# overview_mcu_dev.net
KiCad netlist of a schematic drawn in EAGLE
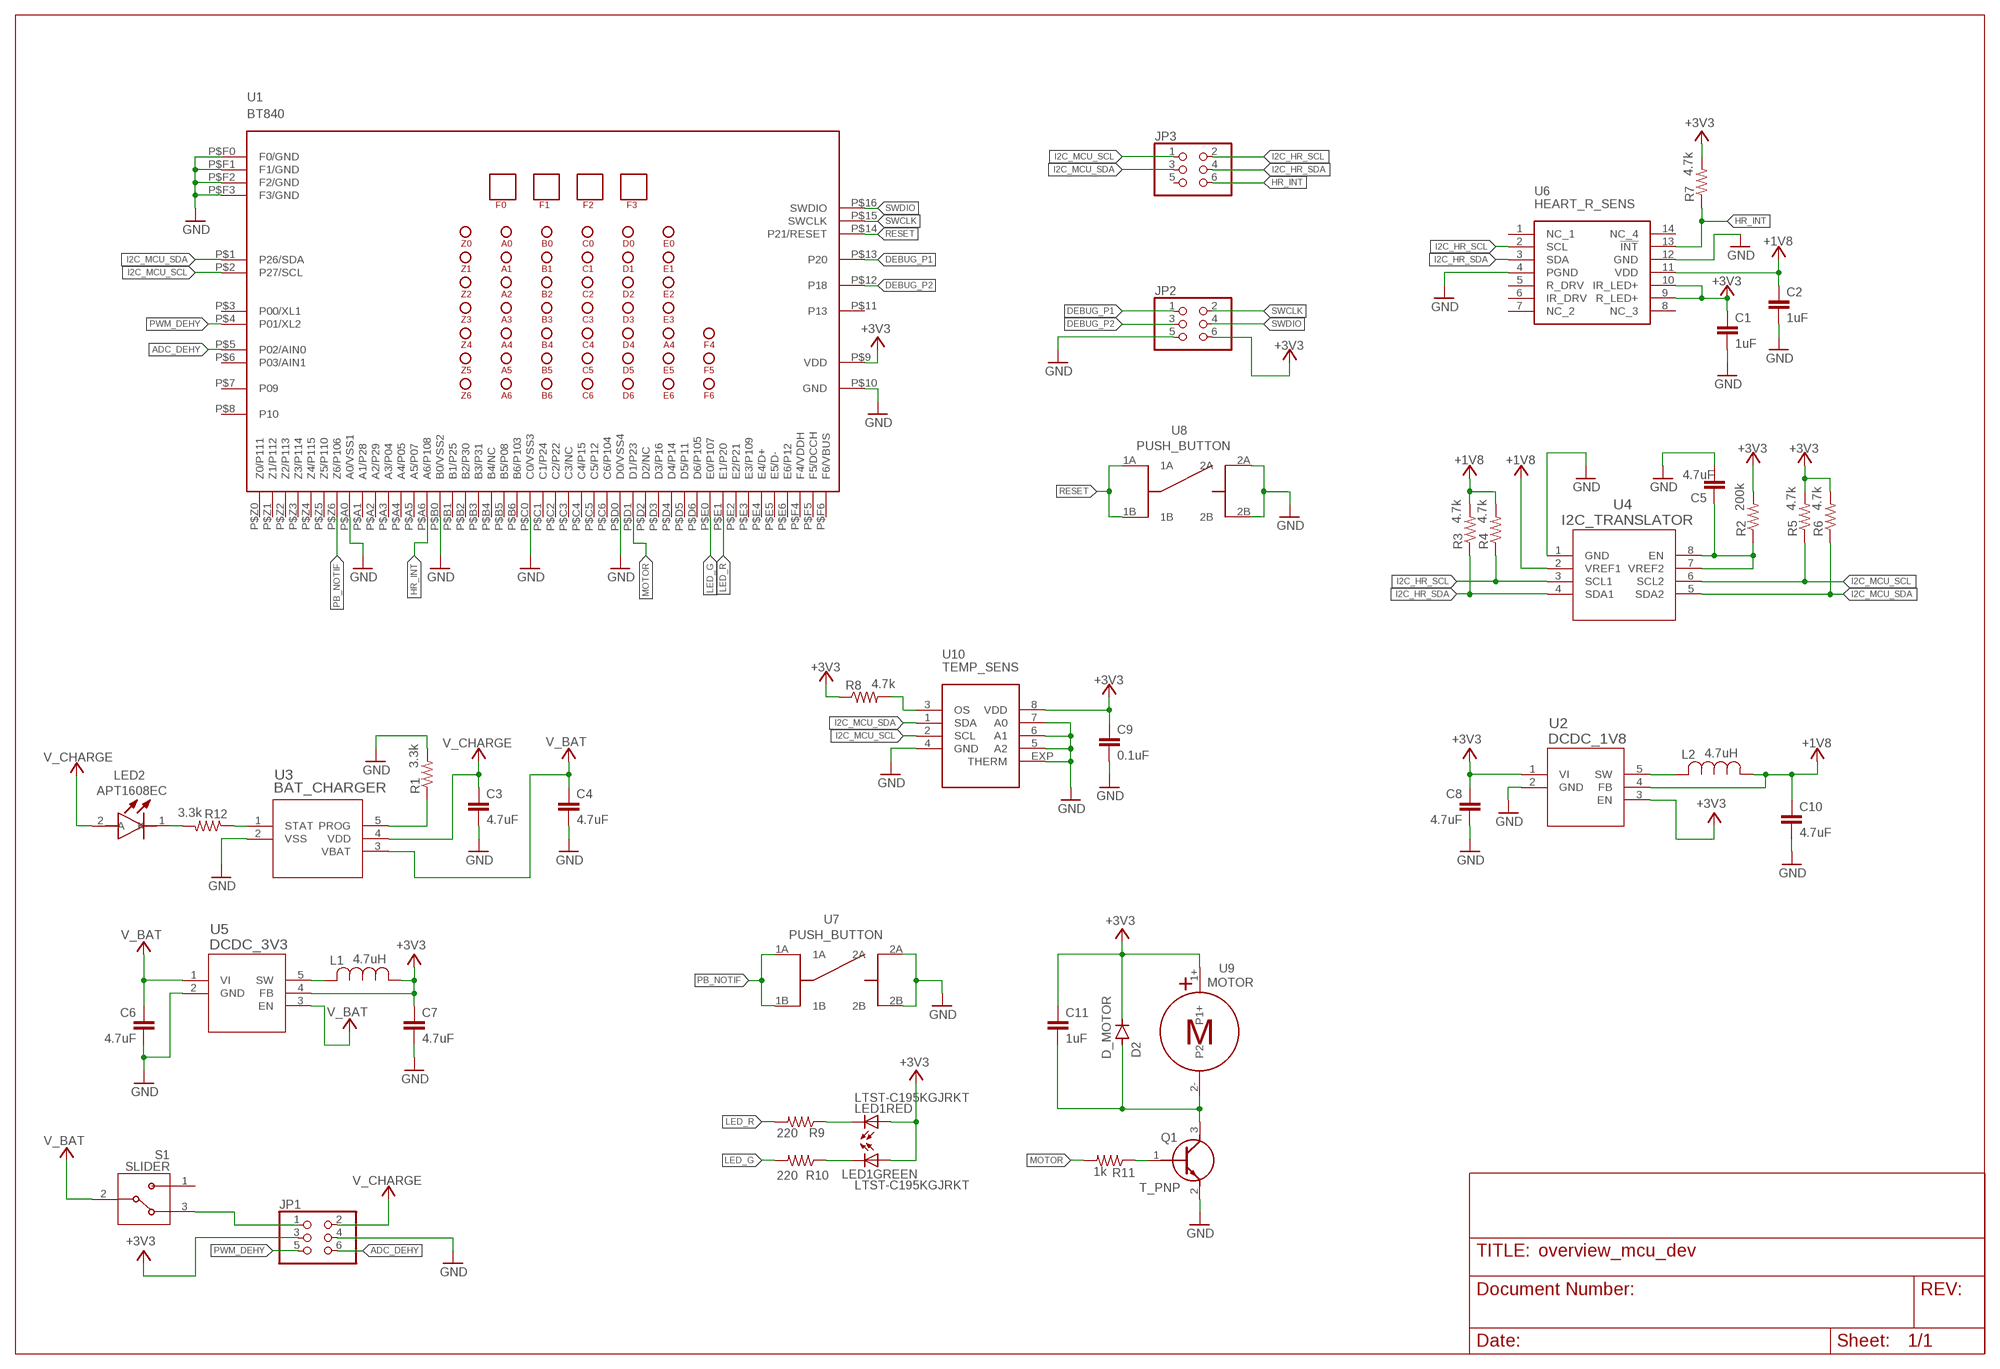
[diagram p0: schematic, sheet 1]

(export (version "E")
  (design (tool "Eeschema 10.0.6"))
  (components
    (comp (ref "C1")
      (value "1uF")
      (footprint "eagle-import:C0402K")
      (libsource (lib "eagle-import") (part "C-EUC0402K"))
    )
    (comp (ref "C2")
      (value "1uF")
      (footprint "eagle-import:C0402K")
      (libsource (lib "eagle-import") (part "C-EUC0402K"))
    )
    (comp (ref "C3")
      (value "4.7uF")
      (footprint "eagle-import:C0402K")
      (libsource (lib "eagle-import") (part "C-EUC0402K"))
    )
    (comp (ref "C4")
      (value "4.7uF")
      (footprint "eagle-import:C0402K")
      (libsource (lib "eagle-import") (part "C-EUC0402K"))
    )
    (comp (ref "C5")
      (value "4.7uF")
      (footprint "eagle-import:C0402K")
      (libsource (lib "eagle-import") (part "C-EUC0402K"))
    )
    (comp (ref "C6")
      (value "4.7uF")
      (footprint "eagle-import:C0402K")
      (libsource (lib "eagle-import") (part "C-EUC0402K"))
    )
    (comp (ref "C7")
      (value "4.7uF")
      (footprint "eagle-import:C0402K")
      (libsource (lib "eagle-import") (part "C-EUC0402K"))
    )
    (comp (ref "C8")
      (value "4.7uF")
      (footprint "eagle-import:C0402K")
      (libsource (lib "eagle-import") (part "C-EUC0402K"))
    )
    (comp (ref "C9")
      (value "0.1uF")
      (footprint "eagle-import:C0402K")
      (libsource (lib "eagle-import") (part "C-EUC0402K"))
    )
    (comp (ref "C10")
      (value "4.7uF")
      (footprint "eagle-import:C0402K")
      (libsource (lib "eagle-import") (part "C-EUC0402K"))
    )
    (comp (ref "C11")
      (value "1uF")
      (footprint "eagle-import:C0402K")
      (libsource (lib "eagle-import") (part "C-EUC0402K"))
    )
    (comp (ref "D2")
      (value "D_MOTOR")
      (footprint "eagle-import:SOD-123_MINI-SMA")
      (libsource (lib "eagle-import") (part "CGRM400-G1"))
    )
    (comp (ref "JP1")
      (value "PINHD-2X3")
      (footprint "eagle-import:2X03")
      (libsource (lib "eagle-import") (part "PINHD-2X3"))
    )
    (comp (ref "JP2")
      (value "PINHD-2X3")
      (footprint "eagle-import:2X03")
      (libsource (lib "eagle-import") (part "PINHD-2X3"))
    )
    (comp (ref "JP3")
      (value "PINHD-2X3")
      (footprint "eagle-import:2X03")
      (libsource (lib "eagle-import") (part "PINHD-2X3"))
    )
    (comp (ref "L1")
      (value "4.7uH")
      (footprint "eagle-import:IND_1608")
      (fields (field (name "MANUFACTURER_PART_NUMBER") "GLFR1608T4R7MLR"))
      (libsource (lib "eagle-import") (part "L_0604"))
    )
    (comp (ref "L2")
      (value "4.7uH")
      (footprint "eagle-import:IND_1608")
      (fields (field (name "MANUFACTURER_PART_NUMBER") "GLFR1608T4R7MLR"))
      (libsource (lib "eagle-import") (part "L_0604"))
    )
    (comp (ref "LED1")
      (value "LTST-C195KGJRKT")
      (footprint "eagle-import:LED-SMT")
      (fields
        (field (name "MANUFACTURER") "Lite-On Inc.")
        (field (name "MANUFACTURER_PART_NUM") "LTST-C195KGJRKT ")
      )
      (libsource (lib "eagle-import") (part "LTST-C195KGJRKT"))
    )
    (comp (ref "LED2")
      (value "APT1608EC")
      (footprint "eagle-import:LEDC1608X85N")
      (fields (field (name "MANUFACTURER") "Kingbright"))
      (libsource (lib "eagle-import") (part "APT1608EC"))
    )
    (comp (ref "Q1")
      (value "T_PNP")
      (footprint "eagle-import:SOT95P240X93-3N")
      (fields
        (field (name "MANUFACTURER") "Micro Commercial Co")
        (field (name "MANUFACTURER_PART_NUM") "MMBT3904-TP ")
      )
      (libsource (lib "eagle-import") (part "T_PNP"))
    )
    (comp (ref "R1")
      (value "3.3k")
      (footprint "eagle-import:R0402")
      (libsource (lib "eagle-import") (part "R-US_R0402"))
    )
    (comp (ref "R2")
      (value "200k")
      (footprint "eagle-import:R0402")
      (libsource (lib "eagle-import") (part "R-US_R0402"))
    )
    (comp (ref "R3")
      (value "4.7k")
      (footprint "eagle-import:R0402")
      (libsource (lib "eagle-import") (part "R-US_R0402"))
    )
    (comp (ref "R4")
      (value "4.7k")
      (footprint "eagle-import:R0402")
      (libsource (lib "eagle-import") (part "R-US_R0402"))
    )
    (comp (ref "R5")
      (value "4.7k")
      (footprint "eagle-import:R0402")
      (libsource (lib "eagle-import") (part "R-US_R0402"))
    )
    (comp (ref "R6")
      (value "4.7k")
      (footprint "eagle-import:R0402")
      (libsource (lib "eagle-import") (part "R-US_R0402"))
    )
    (comp (ref "R7")
      (value "4.7k")
      (footprint "eagle-import:R0402")
      (libsource (lib "eagle-import") (part "R-US_R0402"))
    )
    (comp (ref "R8")
      (value "4.7k")
      (footprint "eagle-import:R0402")
      (libsource (lib "eagle-import") (part "R-US_R0402"))
    )
    (comp (ref "R9")
      (value "220")
      (footprint "eagle-import:R0402")
      (libsource (lib "eagle-import") (part "R-US_R0402"))
    )
    (comp (ref "R10")
      (value "220")
      (footprint "eagle-import:R0402")
      (libsource (lib "eagle-import") (part "R-US_R0402"))
    )
    (comp (ref "R11")
      (value "1k")
      (footprint "eagle-import:R0402")
      (libsource (lib "eagle-import") (part "R-US_R0402"))
    )
    (comp (ref "R12")
      (value "3.3k")
      (footprint "eagle-import:R0402")
      (libsource (lib "eagle-import") (part "R-US_R0402"))
    )
    (comp (ref "S1")
      (value "SLIDER")
      (footprint "eagle-import:SW_CJS-1200TA")
      (fields
        (field (name "MANUFACTURER") "Nidec Copal Electronics")
        (field (name "MANUFACTURER_PART") "CJS-1200TA ")
      )
      (libsource (lib "eagle-import") (part "SLIDER"))
    )
    (comp (ref "U1")
      (value "BT840")
      (footprint "eagle-import:BT840")
      (fields (field (name "MANUFACTURER") "Fanstel"))
      (libsource (lib "eagle-import") (part "BT840"))
    )
    (comp (ref "U2")
      (value "DCDC_1V8")
      (footprint "eagle-import:DBV5")
      (fields
        (field (name "MANUFACTURER") "Texas Instruments")
        (field (name "MANUFACTURER_PART_NUM") "TPS62202DBVR")
      )
      (libsource (lib "eagle-import") (part "DCDC_1V8"))
    )
    (comp (ref "U3")
      (value "BAT_CHARGER")
      (footprint "eagle-import:SOT-23-5_MC")
      (fields
        (field (name "MANUFACTURER") "Microchip")
        (field (name "MANUFACTURER_PART_NUM") "MCP73831T2ACIOT")
      )
      (libsource (lib "eagle-import") (part "BAT_CHARGER"))
    )
    (comp (ref "U4")
      (value "I2C_TRANSLATOR")
      (footprint "eagle-import:DQE8")
      (fields
        (field (name "MANUFACTURER") "Texas Instruments")
        (field (name "MANUFACTURER_PART_NUM") "PCA9306DQER")
      )
      (libsource (lib "eagle-import") (part "I2C_TRANSLATOR"))
    )
    (comp (ref "U5")
      (value "DCDC_3V3")
      (footprint "eagle-import:DBV5")
      (fields
        (field (name "MANUFACTURER") "Texas Instruments")
        (field (name "MANUFACTURER_PART_NUM") "TPS62203DBVR")
      )
      (libsource (lib "eagle-import") (part "DCDC_3V3"))
    )
    (comp (ref "U6")
      (value "HEART_R_SENS")
      (footprint "eagle-import:MAX30102")
      (fields
        (field (name "MANUFACTURER") "Maxim Integrated")
        (field (name "MANUFACTURER_PART_NUM") "MAX30102EFD+")
      )
      (libsource (lib "eagle-import") (part "HEART_R_SENS"))
    )
    (comp (ref "U7")
      (value "PUSH_BUTTON")
      (footprint "eagle-import:PUSH_BUTTON")
      (fields
        (field (name "MANUFACTURER") " Panasonic Electronic Components")
        (field (name "MANUFACTURER_PART_NUM") "EVQ-P7A01P ")
      )
      (libsource (lib "eagle-import") (part "PUSH_BUTTON"))
    )
    (comp (ref "U8")
      (value "PUSH_BUTTON")
      (footprint "eagle-import:PUSH_BUTTON")
      (fields
        (field (name "MANUFACTURER") " Panasonic Electronic Components")
        (field (name "MANUFACTURER_PART_NUM") "EVQ-P7A01P ")
      )
      (libsource (lib "eagle-import") (part "PUSH_BUTTON"))
    )
    (comp (ref "U9")
      (value "MOTOR")
      (footprint "eagle-import:MOTOR")
      (fields
        (field (name "MANUFACTURER") "Jinlong Machinery & Electronics, Inc.")
        (field (name "MANUFACTURER_PART_NUM") "Z4FC1B1301781")
      )
      (libsource (lib "eagle-import") (part "MOTOR"))
    )
    (comp (ref "U10")
      (value "TEMP_SENS")
      (footprint "eagle-import:MAX30205")
      (fields
        (field (name "MANUFACTURER") "Maxim Integrated")
        (field (name "MANUFACTURER_PART_NUM") "MAX30205MTA+")
      )
      (libsource (lib "eagle-import") (part "TEMP_SENS"))
    )
  )
  (nets
    (net (code "1") (name "+1V8") (class "Default")
      (node (ref "C10") (pin "1") (pinfunction "1_1") (pintype "passive"))
      (node (ref "C2") (pin "1") (pinfunction "1_1") (pintype "passive"))
      (node (ref "L2") (pin "1") (pinfunction "1_1") (pintype "passive"))
      (node (ref "R3") (pin "2") (pinfunction "2_2") (pintype "passive"))
      (node (ref "R4") (pin "2") (pinfunction "2_2") (pintype "passive"))
      (node (ref "U2") (pin "4") (pinfunction "FB_4") (pintype "input"))
      (node (ref "U4") (pin "2") (pinfunction "VREF1_2") (pintype "passive"))
      (node (ref "U6") (pin "11") (pinfunction "VDD_11") (pintype "bidirectional"))
    )
    (net (code "2") (name "+3V3") (class "Default")
      (node (ref "C1") (pin "1") (pinfunction "1_1") (pintype "passive"))
      (node (ref "C11") (pin "1") (pinfunction "1_1") (pintype "passive"))
      (node (ref "C7") (pin "1") (pinfunction "1_1") (pintype "passive"))
      (node (ref "C8") (pin "1") (pinfunction "1_1") (pintype "passive"))
      (node (ref "C9") (pin "1") (pinfunction "1_1") (pintype "passive"))
      (node (ref "D2") (pin "C") (pinfunction "C_C") (pintype "passive"))
      (node (ref "JP1") (pin "3") (pinfunction "3_3") (pintype "passive"))
      (node (ref "JP2") (pin "6") (pinfunction "6_6") (pintype "passive"))
      (node (ref "L1") (pin "1") (pinfunction "1_1") (pintype "passive"))
      (node (ref "LED1") (pin "P$1") (pinfunction "A_P$1") (pintype "passive"))
      (node (ref "LED1") (pin "P$2") (pinfunction "A_P$2") (pintype "passive"))
      (node (ref "R2") (pin "2") (pinfunction "2_2") (pintype "passive"))
      (node (ref "R5") (pin "2") (pinfunction "2_2") (pintype "passive"))
      (node (ref "R6") (pin "2") (pinfunction "2_2") (pintype "passive"))
      (node (ref "R7") (pin "2") (pinfunction "2_2") (pintype "passive"))
      (node (ref "R8") (pin "1") (pinfunction "1_1") (pintype "passive"))
      (node (ref "U1") (pin "P$9") (pinfunction "VDD_P$9") (pintype "bidirectional"))
      (node (ref "U10") (pin "8") (pinfunction "VDD_8") (pintype "bidirectional"))
      (node (ref "U2") (pin "1") (pinfunction "VI_1") (pintype "input"))
      (node (ref "U2") (pin "3") (pinfunction "EN_3") (pintype "input"))
      (node (ref "U5") (pin "4") (pinfunction "FB_4") (pintype "input"))
      (node (ref "U6") (pin "10") (pinfunction "IR_LED+_10") (pintype "bidirectional"))
      (node (ref "U6") (pin "9") (pinfunction "R_LED+_9") (pintype "bidirectional"))
      (node (ref "U9") (pin "1+") (pinfunction "P1+_1+") (pintype "bidirectional"))
    )
    (net (code "3") (name "ADC_DEHY") (class "Default")
      (node (ref "JP1") (pin "6") (pinfunction "6_6") (pintype "passive"))
      (node (ref "U1") (pin "P$5") (pinfunction "P02/AIN0_P$5") (pintype "bidirectional"))
    )
    (net (code "4") (name "DEBUG_P1") (class "Default")
      (node (ref "JP2") (pin "1") (pinfunction "1_1") (pintype "passive"))
      (node (ref "U1") (pin "P$13") (pinfunction "P20_P$13") (pintype "bidirectional"))
    )
    (net (code "5") (name "DEBUG_P2") (class "Default")
      (node (ref "JP2") (pin "3") (pinfunction "3_3") (pintype "passive"))
      (node (ref "U1") (pin "P$12") (pinfunction "P18_P$12") (pintype "bidirectional"))
    )
    (net (code "6") (name "GND") (class "Default")
      (node (ref "C1") (pin "2") (pinfunction "2_2") (pintype "passive"))
      (node (ref "C10") (pin "2") (pinfunction "2_2") (pintype "passive"))
      (node (ref "C2") (pin "2") (pinfunction "2_2") (pintype "passive"))
      (node (ref "C3") (pin "2") (pinfunction "2_2") (pintype "passive"))
      (node (ref "C4") (pin "2") (pinfunction "2_2") (pintype "passive"))
      (node (ref "C5") (pin "2") (pinfunction "2_2") (pintype "passive"))
      (node (ref "C6") (pin "2") (pinfunction "2_2") (pintype "passive"))
      (node (ref "C7") (pin "2") (pinfunction "2_2") (pintype "passive"))
      (node (ref "C8") (pin "2") (pinfunction "2_2") (pintype "passive"))
      (node (ref "C9") (pin "2") (pinfunction "2_2") (pintype "passive"))
      (node (ref "JP1") (pin "4") (pinfunction "4_4") (pintype "passive"))
      (node (ref "JP2") (pin "5") (pinfunction "5_5") (pintype "passive"))
      (node (ref "Q1") (pin "2") (pinfunction "E_2") (pintype "bidirectional"))
      (node (ref "R1") (pin "2") (pinfunction "2_2") (pintype "passive"))
      (node (ref "U1") (pin "P$10") (pinfunction "GND_P$10") (pintype "bidirectional"))
      (node (ref "U1") (pin "P$A0") (pinfunction "A0/VSS1_P$A0") (pintype "bidirectional"))
      (node (ref "U1") (pin "P$B0") (pinfunction "B0/VSS2_P$B0") (pintype "bidirectional"))
      (node (ref "U1") (pin "P$C0") (pinfunction "C0/VSS3_P$C0") (pintype "bidirectional"))
      (node (ref "U1") (pin "P$D0") (pinfunction "D0/VSS4_P$D0") (pintype "bidirectional"))
      (node (ref "U1") (pin "P$F0") (pinfunction "F0/GND_P$F0") (pintype "bidirectional"))
      (node (ref "U1") (pin "P$F1") (pinfunction "F1/GND_P$F1") (pintype "bidirectional"))
      (node (ref "U1") (pin "P$F2") (pinfunction "F2/GND_P$F2") (pintype "bidirectional"))
      (node (ref "U1") (pin "P$F3") (pinfunction "F3/GND_P$F3") (pintype "bidirectional"))
      (node (ref "U10") (pin "4") (pinfunction "GND_4") (pintype "bidirectional"))
      (node (ref "U10") (pin "5") (pinfunction "A2_5") (pintype "bidirectional"))
      (node (ref "U10") (pin "6") (pinfunction "A1_6") (pintype "bidirectional"))
      (node (ref "U10") (pin "7") (pinfunction "A0_7") (pintype "bidirectional"))
      (node (ref "U10") (pin "EXP") (pinfunction "THERM_EXP") (pintype "bidirectional"))
      (node (ref "U2") (pin "2") (pinfunction "GND_2") (pintype "power_in"))
      (node (ref "U3") (pin "2") (pinfunction "VSS_2") (pintype "passive"))
      (node (ref "U4") (pin "1") (pinfunction "GND_1") (pintype "power_in"))
      (node (ref "U5") (pin "2") (pinfunction "GND_2") (pintype "power_in"))
      (node (ref "U6") (pin "12") (pinfunction "GND_12") (pintype "bidirectional"))
      (node (ref "U6") (pin "4") (pinfunction "PGND_4") (pintype "bidirectional"))
      (node (ref "U7") (pin "2A") (pinfunction "2A_2A") (pintype "bidirectional"))
      (node (ref "U7") (pin "2B") (pinfunction "2B_2B") (pintype "bidirectional"))
      (node (ref "U8") (pin "2A") (pinfunction "2A_2A") (pintype "bidirectional"))
      (node (ref "U8") (pin "2B") (pinfunction "2B_2B") (pintype "bidirectional"))
    )
    (net (code "7") (name "HR_INT") (class "Default")
      (node (ref "JP3") (pin "6") (pinfunction "6_6") (pintype "passive"))
      (node (ref "R7") (pin "1") (pinfunction "1_1") (pintype "passive"))
      (node (ref "U1") (pin "P$A6") (pinfunction "A6/P108_P$A6") (pintype "bidirectional"))
      (node (ref "U6") (pin "13") (pinfunction "~{INT}_13") (pintype "bidirectional"))
    )
    (net (code "8") (name "I2C_HR_SCL") (class "Default")
      (node (ref "JP3") (pin "2") (pinfunction "2_2") (pintype "passive"))
      (node (ref "R4") (pin "1") (pinfunction "1_1") (pintype "passive"))
      (node (ref "U4") (pin "3") (pinfunction "SCL1_3") (pintype "passive"))
      (node (ref "U6") (pin "2") (pinfunction "SCL_2") (pintype "bidirectional"))
    )
    (net (code "9") (name "I2C_HR_SDA") (class "Default")
      (node (ref "JP3") (pin "4") (pinfunction "4_4") (pintype "passive"))
      (node (ref "R3") (pin "1") (pinfunction "1_1") (pintype "passive"))
      (node (ref "U4") (pin "4") (pinfunction "SDA1_4") (pintype "passive"))
      (node (ref "U6") (pin "3") (pinfunction "SDA_3") (pintype "bidirectional"))
    )
    (net (code "10") (name "I2C_MCU_SCL") (class "Default")
      (node (ref "JP3") (pin "1") (pinfunction "1_1") (pintype "passive"))
      (node (ref "R5") (pin "1") (pinfunction "1_1") (pintype "passive"))
      (node (ref "U1") (pin "P$2") (pinfunction "P27/SCL_P$2") (pintype "bidirectional"))
      (node (ref "U10") (pin "2") (pinfunction "SCL_2") (pintype "bidirectional"))
      (node (ref "U4") (pin "6") (pinfunction "SCL2_6") (pintype "passive"))
    )
    (net (code "11") (name "I2C_MCU_SDA") (class "Default")
      (node (ref "JP3") (pin "3") (pinfunction "3_3") (pintype "passive"))
      (node (ref "R6") (pin "1") (pinfunction "1_1") (pintype "passive"))
      (node (ref "U1") (pin "P$1") (pinfunction "P26/SDA_P$1") (pintype "bidirectional"))
      (node (ref "U10") (pin "1") (pinfunction "SDA_1") (pintype "bidirectional"))
      (node (ref "U4") (pin "5") (pinfunction "SDA2_5") (pintype "passive"))
    )
    (net (code "12") (name "LED_G") (class "Default")
      (node (ref "R10") (pin "2") (pinfunction "2_2") (pintype "passive"))
      (node (ref "U1") (pin "P$E0") (pinfunction "E0/P107_P$E0") (pintype "bidirectional"))
    )
    (net (code "13") (name "LED_R") (class "Default")
      (node (ref "R9") (pin "2") (pinfunction "2_2") (pintype "passive"))
      (node (ref "U1") (pin "P$E1") (pinfunction "E1/P20_P$E1") (pintype "bidirectional"))
    )
    (net (code "14") (name "MOTOR") (class "Default")
      (node (ref "R11") (pin "2") (pinfunction "2_2") (pintype "passive"))
      (node (ref "U1") (pin "P$D1") (pinfunction "D1/P23_P$D1") (pintype "bidirectional"))
    )
    (net (code "15") (name "Net-(JP1-Pad1)") (class "Default")
      (node (ref "JP1") (pin "1") (pinfunction "1_1") (pintype "passive"))
      (node (ref "S1") (pin "3") (pinfunction "3_3") (pintype "passive"))
    )
    (net (code "16") (name "Net-(LED1A-C)") (class "Default")
      (node (ref "LED1") (pin "P$3") (pinfunction "C_P$3") (pintype "passive"))
      (node (ref "R10") (pin "1") (pinfunction "1_1") (pintype "passive"))
    )
    (net (code "17") (name "Net-(LED1B-C)") (class "Default")
      (node (ref "LED1") (pin "P$4") (pinfunction "C_P$4") (pintype "passive"))
      (node (ref "R9") (pin "1") (pinfunction "1_1") (pintype "passive"))
    )
    (net (code "18") (name "Net-(LED2-K)") (class "Default")
      (node (ref "LED2") (pin "1") (pinfunction "K_1") (pintype "bidirectional"))
      (node (ref "R12") (pin "2") (pinfunction "2_2") (pintype "passive"))
    )
    (net (code "19") (name "Net-(Q1-B)") (class "Default")
      (node (ref "Q1") (pin "1") (pinfunction "B_1") (pintype "bidirectional"))
      (node (ref "R11") (pin "1") (pinfunction "1_1") (pintype "passive"))
    )
    (net (code "20") (name "Net-(Q1-C)") (class "Default")
      (node (ref "C11") (pin "2") (pinfunction "2_2") (pintype "passive"))
      (node (ref "D2") (pin "A") (pinfunction "A_A") (pintype "passive"))
      (node (ref "Q1") (pin "3") (pinfunction "C_3") (pintype "bidirectional"))
      (node (ref "U9") (pin "2-") (pinfunction "P2-_2-") (pintype "bidirectional"))
    )
    (net (code "21") (name "Net-(U2-SW)") (class "Default")
      (node (ref "L2") (pin "2") (pinfunction "2_2") (pintype "passive"))
      (node (ref "U2") (pin "5") (pinfunction "SW_5") (pintype "bidirectional"))
    )
    (net (code "22") (name "Net-(U3-PROG)") (class "Default")
      (node (ref "R1") (pin "1") (pinfunction "1_1") (pintype "passive"))
      (node (ref "U3") (pin "5") (pinfunction "PROG_5") (pintype "passive"))
    )
    (net (code "23") (name "Net-(U3-STAT)") (class "Default")
      (node (ref "R12") (pin "1") (pinfunction "1_1") (pintype "passive"))
      (node (ref "U3") (pin "1") (pinfunction "STAT_1") (pintype "passive"))
    )
    (net (code "24") (name "Net-(U4-EN)") (class "Default")
      (node (ref "C5") (pin "1") (pinfunction "1_1") (pintype "passive"))
      (node (ref "R2") (pin "1") (pinfunction "1_1") (pintype "passive"))
      (node (ref "U4") (pin "7") (pinfunction "VREF2_7") (pintype "passive"))
      (node (ref "U4") (pin "8") (pinfunction "EN_8") (pintype "passive"))
    )
    (net (code "25") (name "Net-(U5-SW)") (class "Default")
      (node (ref "L1") (pin "2") (pinfunction "2_2") (pintype "passive"))
      (node (ref "U5") (pin "5") (pinfunction "SW_5") (pintype "bidirectional"))
    )
    (net (code "26") (name "Net-(U10-OS)") (class "Default")
      (node (ref "R8") (pin "2") (pinfunction "2_2") (pintype "passive"))
      (node (ref "U10") (pin "3") (pinfunction "OS_3") (pintype "bidirectional"))
    )
    (net (code "27") (name "PB_NOTIF") (class "Default")
      (node (ref "U1") (pin "P$Z6") (pinfunction "Z6/P106_P$Z6") (pintype "bidirectional"))
      (node (ref "U7") (pin "1A") (pinfunction "1A_1A") (pintype "bidirectional"))
      (node (ref "U7") (pin "1B") (pinfunction "1B_1B") (pintype "bidirectional"))
    )
    (net (code "28") (name "PWM_DEHY") (class "Default")
      (node (ref "JP1") (pin "5") (pinfunction "5_5") (pintype "passive"))
      (node (ref "U1") (pin "P$4") (pinfunction "P01/XL2_P$4") (pintype "bidirectional"))
    )
    (net (code "29") (name "RESET") (class "Default")
      (node (ref "U1") (pin "P$14") (pinfunction "P21/RESET_P$14") (pintype "bidirectional"))
      (node (ref "U8") (pin "1A") (pinfunction "1A_1A") (pintype "bidirectional"))
      (node (ref "U8") (pin "1B") (pinfunction "1B_1B") (pintype "bidirectional"))
    )
    (net (code "30") (name "SWCLK") (class "Default")
      (node (ref "JP2") (pin "2") (pinfunction "2_2") (pintype "passive"))
      (node (ref "U1") (pin "P$15") (pinfunction "SWCLK_P$15") (pintype "bidirectional"))
    )
    (net (code "31") (name "SWDIO") (class "Default")
      (node (ref "JP2") (pin "4") (pinfunction "4_4") (pintype "passive"))
      (node (ref "U1") (pin "P$16") (pinfunction "SWDIO_P$16") (pintype "bidirectional"))
    )
    (net (code "32") (name "V_BAT") (class "Default")
      (node (ref "C4") (pin "1") (pinfunction "1_1") (pintype "passive"))
      (node (ref "C6") (pin "1") (pinfunction "1_1") (pintype "passive"))
      (node (ref "S1") (pin "2") (pinfunction "2_2") (pintype "passive"))
      (node (ref "U3") (pin "3") (pinfunction "VBAT_3") (pintype "passive"))
      (node (ref "U5") (pin "1") (pinfunction "VI_1") (pintype "input"))
      (node (ref "U5") (pin "3") (pinfunction "EN_3") (pintype "input"))
    )
    (net (code "33") (name "V_CHARGE") (class "Default")
      (node (ref "C3") (pin "1") (pinfunction "1_1") (pintype "passive"))
      (node (ref "JP1") (pin "2") (pinfunction "2_2") (pintype "passive"))
      (node (ref "LED2") (pin "2") (pinfunction "A_2") (pintype "bidirectional"))
      (node (ref "U3") (pin "4") (pinfunction "VDD_4") (pintype "passive"))
    )
    (net (code "34") (name "unconnected-(JP3-Pad5)") (class "Default")
      (node (ref "JP3") (pin "5") (pinfunction "5_5") (pintype "passive"))
    )
    (net (code "35") (name "unconnected-(S1-Pad1)") (class "Default")
      (node (ref "S1") (pin "1") (pinfunction "1_1") (pintype "passive"))
    )
    (net (code "36") (name "unconnected-(U1-A1{slash}P28-PadP$A1)") (class "Default")
      (node (ref "U1") (pin "P$A1") (pinfunction "A1/P28_P$A1") (pintype "bidirectional"))
    )
    (net (code "37") (name "unconnected-(U1-A2{slash}P29-PadP$A2)") (class "Default")
      (node (ref "U1") (pin "P$A2") (pinfunction "A2/P29_P$A2") (pintype "bidirectional"))
    )
    (net (code "38") (name "unconnected-(U1-A3{slash}P04-PadP$A3)") (class "Default")
      (node (ref "U1") (pin "P$A3") (pinfunction "A3/P04_P$A3") (pintype "bidirectional"))
    )
    (net (code "39") (name "unconnected-(U1-A4{slash}P05-PadP$A4)") (class "Default")
      (node (ref "U1") (pin "P$A4") (pinfunction "A4/P05_P$A4") (pintype "bidirectional"))
    )
    (net (code "40") (name "unconnected-(U1-A5{slash}P07-PadP$A5)") (class "Default")
      (node (ref "U1") (pin "P$A5") (pinfunction "A5/P07_P$A5") (pintype "bidirectional"))
    )
    (net (code "41") (name "unconnected-(U1-B1{slash}P25-PadP$B1)") (class "Default")
      (node (ref "U1") (pin "P$B1") (pinfunction "B1/P25_P$B1") (pintype "bidirectional"))
    )
    (net (code "42") (name "unconnected-(U1-B2{slash}P30-PadP$B2)") (class "Default")
      (node (ref "U1") (pin "P$B2") (pinfunction "B2/P30_P$B2") (pintype "bidirectional"))
    )
    (net (code "43") (name "unconnected-(U1-B3{slash}P31-PadP$B3)") (class "Default")
      (node (ref "U1") (pin "P$B3") (pinfunction "B3/P31_P$B3") (pintype "bidirectional"))
    )
    (net (code "44") (name "unconnected-(U1-B4{slash}NC-PadP$B4)") (class "Default")
      (node (ref "U1") (pin "P$B4") (pinfunction "B4/NC_P$B4") (pintype "bidirectional"))
    )
    (net (code "45") (name "unconnected-(U1-B5{slash}P08-PadP$B5)") (class "Default")
      (node (ref "U1") (pin "P$B5") (pinfunction "B5/P08_P$B5") (pintype "bidirectional"))
    )
    (net (code "46") (name "unconnected-(U1-B6{slash}P103-PadP$B6)") (class "Default")
      (node (ref "U1") (pin "P$B6") (pinfunction "B6/P103_P$B6") (pintype "bidirectional"))
    )
    (net (code "47") (name "unconnected-(U1-C1{slash}P24-PadP$C1)") (class "Default")
      (node (ref "U1") (pin "P$C1") (pinfunction "C1/P24_P$C1") (pintype "bidirectional"))
    )
    (net (code "48") (name "unconnected-(U1-C2{slash}P22-PadP$C2)") (class "Default")
      (node (ref "U1") (pin "P$C2") (pinfunction "C2/P22_P$C2") (pintype "bidirectional"))
    )
    (net (code "49") (name "unconnected-(U1-C3{slash}NC-PadP$C3)") (class "Default")
      (node (ref "U1") (pin "P$C3") (pinfunction "C3/NC_P$C3") (pintype "bidirectional"))
    )
    (net (code "50") (name "unconnected-(U1-C4{slash}P15-PadP$C4)") (class "Default")
      (node (ref "U1") (pin "P$C4") (pinfunction "C4/P15_P$C4") (pintype "bidirectional"))
    )
    (net (code "51") (name "unconnected-(U1-C5{slash}P12-PadP$C5)") (class "Default")
      (node (ref "U1") (pin "P$C5") (pinfunction "C5/P12_P$C5") (pintype "bidirectional"))
    )
    (net (code "52") (name "unconnected-(U1-C6{slash}P104-PadP$C6)") (class "Default")
      (node (ref "U1") (pin "P$C6") (pinfunction "C6/P104_P$C6") (pintype "bidirectional"))
    )
    (net (code "53") (name "unconnected-(U1-D2{slash}NC-PadP$D2)") (class "Default")
      (node (ref "U1") (pin "P$D2") (pinfunction "D2/NC_P$D2") (pintype "bidirectional"))
    )
    (net (code "54") (name "unconnected-(U1-D3{slash}P16-PadP$D3)") (class "Default")
      (node (ref "U1") (pin "P$D3") (pinfunction "D3/P16_P$D3") (pintype "bidirectional"))
    )
    (net (code "55") (name "unconnected-(U1-D4{slash}P14-PadP$D4)") (class "Default")
      (node (ref "U1") (pin "P$D4") (pinfunction "D4/P14_P$D4") (pintype "bidirectional"))
    )
    (net (code "56") (name "unconnected-(U1-D5{slash}P11-PadP$D5)") (class "Default")
      (node (ref "U1") (pin "P$D5") (pinfunction "D5/P11_P$D5") (pintype "bidirectional"))
    )
    (net (code "57") (name "unconnected-(U1-D6{slash}P105-PadP$D6)") (class "Default")
      (node (ref "U1") (pin "P$D6") (pinfunction "D6/P105_P$D6") (pintype "bidirectional"))
    )
    (net (code "58") (name "unconnected-(U1-E2{slash}P21-PadP$E2)") (class "Default")
      (node (ref "U1") (pin "P$E2") (pinfunction "E2/P21_P$E2") (pintype "bidirectional"))
    )
    (net (code "59") (name "unconnected-(U1-E3{slash}P109-PadP$E3)") (class "Default")
      (node (ref "U1") (pin "P$E3") (pinfunction "E3/P109_P$E3") (pintype "bidirectional"))
    )
    (net (code "60") (name "unconnected-(U1-E4{slash}D+-PadP$E4)") (class "Default")
      (node (ref "U1") (pin "P$E4") (pinfunction "E4/D+_P$E4") (pintype "bidirectional"))
    )
    (net (code "61") (name "unconnected-(U1-E5{slash}D--PadP$E5)") (class "Default")
      (node (ref "U1") (pin "P$E5") (pinfunction "E5/D-_P$E5") (pintype "bidirectional"))
    )
    (net (code "62") (name "unconnected-(U1-E6{slash}P12-PadP$E6)") (class "Default")
      (node (ref "U1") (pin "P$E6") (pinfunction "E6/P12_P$E6") (pintype "bidirectional"))
    )
    (net (code "63") (name "unconnected-(U1-F4{slash}VDDH-PadP$F4)") (class "Default")
      (node (ref "U1") (pin "P$F4") (pinfunction "F4/VDDH_P$F4") (pintype "bidirectional"))
    )
    (net (code "64") (name "unconnected-(U1-F5{slash}DCCH-PadP$F5)") (class "Default")
      (node (ref "U1") (pin "P$F5") (pinfunction "F5/DCCH_P$F5") (pintype "bidirectional"))
    )
    (net (code "65") (name "unconnected-(U1-F6{slash}VBUS-PadP$F6)") (class "Default")
      (node (ref "U1") (pin "P$F6") (pinfunction "F6/VBUS_P$F6") (pintype "bidirectional"))
    )
    (net (code "66") (name "unconnected-(U1-P00{slash}XL1-PadP$3)") (class "Default")
      (node (ref "U1") (pin "P$3") (pinfunction "P00/XL1_P$3") (pintype "bidirectional"))
    )
    (net (code "67") (name "unconnected-(U1-P03{slash}AIN1-PadP$6)") (class "Default")
      (node (ref "U1") (pin "P$6") (pinfunction "P03/AIN1_P$6") (pintype "bidirectional"))
    )
    (net (code "68") (name "unconnected-(U1-P09-PadP$7)") (class "Default")
      (node (ref "U1") (pin "P$7") (pinfunction "P09_P$7") (pintype "bidirectional"))
    )
    (net (code "69") (name "unconnected-(U1-P10-PadP$8)") (class "Default")
      (node (ref "U1") (pin "P$8") (pinfunction "P10_P$8") (pintype "bidirectional"))
    )
    (net (code "70") (name "unconnected-(U1-P13-PadP$11)") (class "Default")
      (node (ref "U1") (pin "P$11") (pinfunction "P13_P$11") (pintype "bidirectional"))
    )
    (net (code "71") (name "unconnected-(U1-Z0{slash}P111-PadP$Z0)") (class "Default")
      (node (ref "U1") (pin "P$Z0") (pinfunction "Z0/P111_P$Z0") (pintype "bidirectional"))
    )
    (net (code "72") (name "unconnected-(U1-Z1{slash}P112-PadP$Z1)") (class "Default")
      (node (ref "U1") (pin "P$Z1") (pinfunction "Z1/P112_P$Z1") (pintype "bidirectional"))
    )
    (net (code "73") (name "unconnected-(U1-Z2{slash}P113-PadP$Z2)") (class "Default")
      (node (ref "U1") (pin "P$Z2") (pinfunction "Z2/P113_P$Z2") (pintype "bidirectional"))
    )
    (net (code "74") (name "unconnected-(U1-Z3{slash}P114-PadP$Z3)") (class "Default")
      (node (ref "U1") (pin "P$Z3") (pinfunction "Z3/P114_P$Z3") (pintype "bidirectional"))
    )
    (net (code "75") (name "unconnected-(U1-Z4{slash}P115-PadP$Z4)") (class "Default")
      (node (ref "U1") (pin "P$Z4") (pinfunction "Z4/P115_P$Z4") (pintype "bidirectional"))
    )
    (net (code "76") (name "unconnected-(U1-Z5{slash}P110-PadP$Z5)") (class "Default")
      (node (ref "U1") (pin "P$Z5") (pinfunction "Z5/P110_P$Z5") (pintype "bidirectional"))
    )
    (net (code "77") (name "unconnected-(U6-IR_DRV-Pad6)") (class "Default")
      (node (ref "U6") (pin "6") (pinfunction "IR_DRV_6") (pintype "bidirectional"))
    )
    (net (code "78") (name "unconnected-(U6-NC_1-Pad1)") (class "Default")
      (node (ref "U6") (pin "1") (pinfunction "NC_1_1") (pintype "bidirectional"))
    )
    (net (code "79") (name "unconnected-(U6-NC_2-Pad7)") (class "Default")
      (node (ref "U6") (pin "7") (pinfunction "NC_2_7") (pintype "bidirectional"))
    )
    (net (code "80") (name "unconnected-(U6-NC_3-Pad8)") (class "Default")
      (node (ref "U6") (pin "8") (pinfunction "NC_3_8") (pintype "bidirectional"))
    )
    (net (code "81") (name "unconnected-(U6-NC_4-Pad14)") (class "Default")
      (node (ref "U6") (pin "14") (pinfunction "NC_4_14") (pintype "bidirectional"))
    )
    (net (code "82") (name "unconnected-(U6-R_DRV-Pad5)") (class "Default")
      (node (ref "U6") (pin "5") (pinfunction "R_DRV_5") (pintype "bidirectional"))
    )
  )
)
